# ferrofluide_COUAPEL.net
KiCad netlist of a schematic drawn in EAGLE
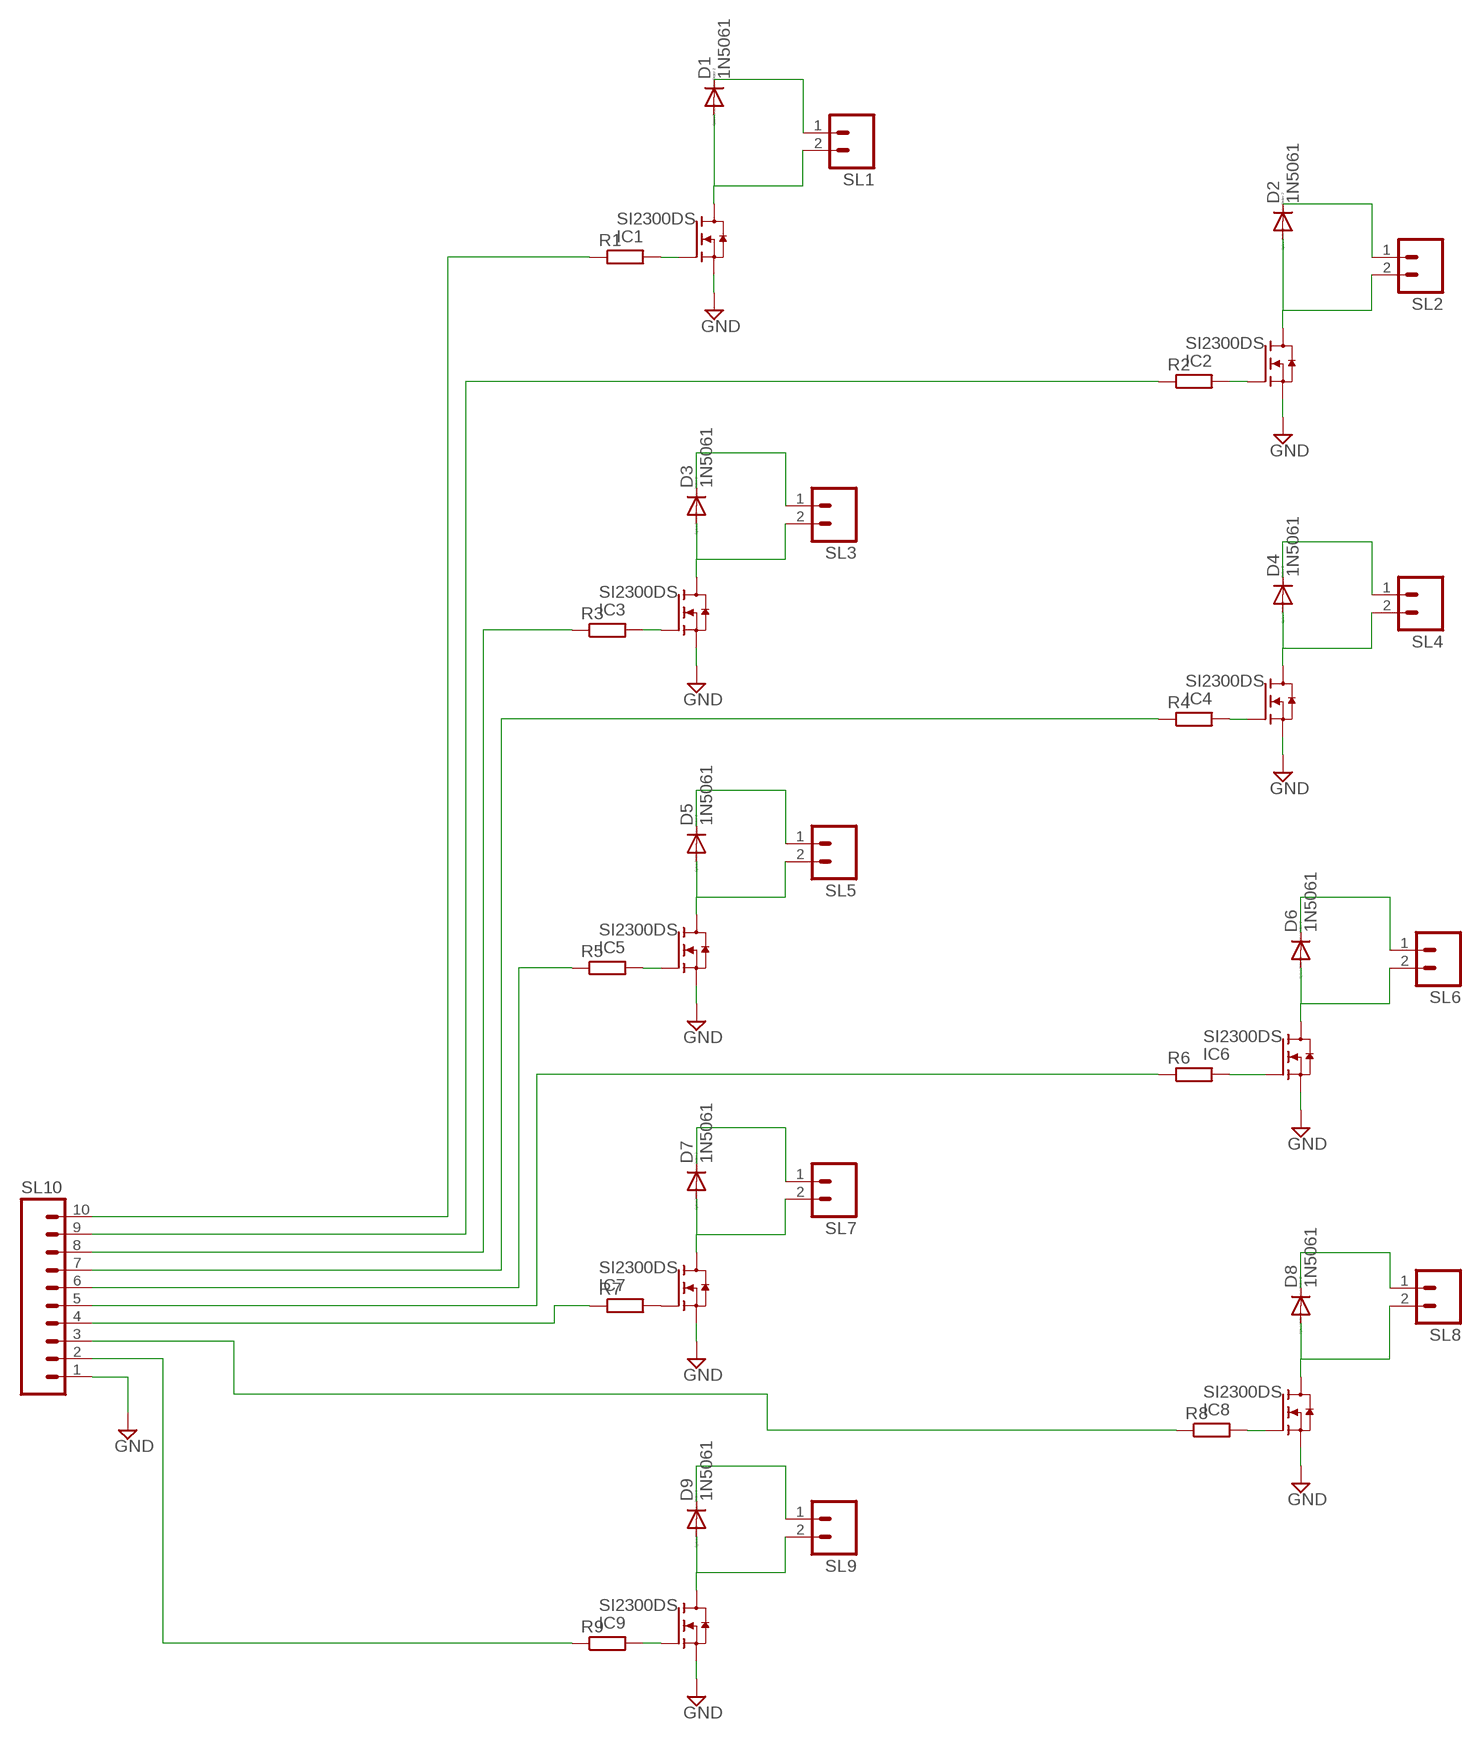
[diagram p0: schematic, sheet 1]

(export (version "E")
  (design (tool "Eeschema 10.0.6"))
  (components
    (comp (ref "D1")
      (value "1N5061")
      (footprint "eagle-import:SOD57-10")
      (libsource (lib "eagle-import") (part "1N5061"))
    )
    (comp (ref "D2")
      (value "1N5061")
      (footprint "eagle-import:SOD57-10")
      (libsource (lib "eagle-import") (part "1N5061"))
    )
    (comp (ref "D3")
      (value "1N5061")
      (footprint "eagle-import:SOD57-10")
      (libsource (lib "eagle-import") (part "1N5061"))
    )
    (comp (ref "D4")
      (value "1N5061")
      (footprint "eagle-import:SOD57-10")
      (libsource (lib "eagle-import") (part "1N5061"))
    )
    (comp (ref "D5")
      (value "1N5061")
      (footprint "eagle-import:SOD57-10")
      (libsource (lib "eagle-import") (part "1N5061"))
    )
    (comp (ref "D6")
      (value "1N5061")
      (footprint "eagle-import:SOD57-10")
      (libsource (lib "eagle-import") (part "1N5061"))
    )
    (comp (ref "D7")
      (value "1N5061")
      (footprint "eagle-import:SOD57-10")
      (libsource (lib "eagle-import") (part "1N5061"))
    )
    (comp (ref "D8")
      (value "1N5061")
      (footprint "eagle-import:SOD57-10")
      (libsource (lib "eagle-import") (part "1N5061"))
    )
    (comp (ref "D9")
      (value "1N5061")
      (footprint "eagle-import:SOD57-10")
      (libsource (lib "eagle-import") (part "1N5061"))
    )
    (comp (ref "IC1")
      (value "SI2300DS")
      (footprint "eagle-import:SOT23")
      (libsource (lib "eagle-import") (part "SI2300DS"))
    )
    (comp (ref "IC2")
      (value "SI2300DS")
      (footprint "eagle-import:SOT23")
      (libsource (lib "eagle-import") (part "SI2300DS"))
    )
    (comp (ref "IC3")
      (value "SI2300DS")
      (footprint "eagle-import:SOT23")
      (libsource (lib "eagle-import") (part "SI2300DS"))
    )
    (comp (ref "IC4")
      (value "SI2300DS")
      (footprint "eagle-import:SOT23")
      (libsource (lib "eagle-import") (part "SI2300DS"))
    )
    (comp (ref "IC5")
      (value "SI2300DS")
      (footprint "eagle-import:SOT23")
      (libsource (lib "eagle-import") (part "SI2300DS"))
    )
    (comp (ref "IC6")
      (value "SI2300DS")
      (footprint "eagle-import:SOT23")
      (libsource (lib "eagle-import") (part "SI2300DS"))
    )
    (comp (ref "IC7")
      (value "SI2300DS")
      (footprint "eagle-import:SOT23")
      (libsource (lib "eagle-import") (part "SI2300DS"))
    )
    (comp (ref "IC8")
      (value "SI2300DS")
      (footprint "eagle-import:SOT23")
      (libsource (lib "eagle-import") (part "SI2300DS"))
    )
    (comp (ref "IC9")
      (value "SI2300DS")
      (footprint "eagle-import:SOT23")
      (libsource (lib "eagle-import") (part "SI2300DS"))
    )
    (comp (ref "R1")
      (value "R-EU_0207/12")
      (footprint "eagle-import:0207_12")
      (libsource (lib "eagle-import") (part "R-EU_0207/12"))
    )
    (comp (ref "R2")
      (value "R-EU_0207/12")
      (footprint "eagle-import:0207_12")
      (libsource (lib "eagle-import") (part "R-EU_0207/12"))
    )
    (comp (ref "R3")
      (value "R-EU_0207/12")
      (footprint "eagle-import:0207_12")
      (libsource (lib "eagle-import") (part "R-EU_0207/12"))
    )
    (comp (ref "R4")
      (value "R-EU_0207/12")
      (footprint "eagle-import:0207_12")
      (libsource (lib "eagle-import") (part "R-EU_0207/12"))
    )
    (comp (ref "R5")
      (value "R-EU_0207/12")
      (footprint "eagle-import:0207_12")
      (libsource (lib "eagle-import") (part "R-EU_0207/12"))
    )
    (comp (ref "R6")
      (value "R-EU_0207/12")
      (footprint "eagle-import:0207_12")
      (libsource (lib "eagle-import") (part "R-EU_0207/12"))
    )
    (comp (ref "R7")
      (value "R-EU_0207/12")
      (footprint "eagle-import:0207_12")
      (libsource (lib "eagle-import") (part "R-EU_0207/12"))
    )
    (comp (ref "R8")
      (value "R-EU_0207/12")
      (footprint "eagle-import:0207_12")
      (libsource (lib "eagle-import") (part "R-EU_0207/12"))
    )
    (comp (ref "R9")
      (value "R-EU_0207/12")
      (footprint "eagle-import:0207_12")
      (libsource (lib "eagle-import") (part "R-EU_0207/12"))
    )
    (comp (ref "SL1")
      (value "M02")
      (footprint "eagle-import:02P")
      (libsource (lib "eagle-import") (part "M02"))
    )
    (comp (ref "SL2")
      (value "M02")
      (footprint "eagle-import:02P")
      (libsource (lib "eagle-import") (part "M02"))
    )
    (comp (ref "SL3")
      (value "M02")
      (footprint "eagle-import:02P")
      (libsource (lib "eagle-import") (part "M02"))
    )
    (comp (ref "SL4")
      (value "M02")
      (footprint "eagle-import:02P")
      (libsource (lib "eagle-import") (part "M02"))
    )
    (comp (ref "SL5")
      (value "M02")
      (footprint "eagle-import:02P")
      (libsource (lib "eagle-import") (part "M02"))
    )
    (comp (ref "SL6")
      (value "M02")
      (footprint "eagle-import:02P")
      (libsource (lib "eagle-import") (part "M02"))
    )
    (comp (ref "SL7")
      (value "M02")
      (footprint "eagle-import:02P")
      (libsource (lib "eagle-import") (part "M02"))
    )
    (comp (ref "SL8")
      (value "M02")
      (footprint "eagle-import:02P")
      (libsource (lib "eagle-import") (part "M02"))
    )
    (comp (ref "SL9")
      (value "M02")
      (footprint "eagle-import:02P")
      (libsource (lib "eagle-import") (part "M02"))
    )
    (comp (ref "SL10")
      (value "M10")
      (footprint "eagle-import:10P")
      (libsource (lib "eagle-import") (part "M10"))
    )
  )
  (nets
    (net (code "1") (name "GND") (class "Default")
      (node (ref "IC1") (pin "2") (pinfunction "S_2") (pintype "passive"))
      (node (ref "IC2") (pin "2") (pinfunction "S_2") (pintype "passive"))
      (node (ref "IC3") (pin "2") (pinfunction "S_2") (pintype "passive"))
      (node (ref "IC4") (pin "2") (pinfunction "S_2") (pintype "passive"))
      (node (ref "IC5") (pin "2") (pinfunction "S_2") (pintype "passive"))
      (node (ref "IC6") (pin "2") (pinfunction "S_2") (pintype "passive"))
      (node (ref "IC7") (pin "2") (pinfunction "S_2") (pintype "passive"))
      (node (ref "IC8") (pin "2") (pinfunction "S_2") (pintype "passive"))
      (node (ref "IC9") (pin "2") (pinfunction "S_2") (pintype "passive"))
      (node (ref "SL10") (pin "1") (pinfunction "1_1") (pintype "passive"))
    )
    (net (code "2") (name "Net-(D1-PadC)") (class "Default")
      (node (ref "D1") (pin "C") (pinfunction "C_C") (pintype "passive"))
      (node (ref "SL1") (pin "1") (pinfunction "1_1") (pintype "passive"))
    )
    (net (code "3") (name "Net-(D2-PadC)") (class "Default")
      (node (ref "D2") (pin "C") (pinfunction "C_C") (pintype "passive"))
      (node (ref "SL2") (pin "1") (pinfunction "1_1") (pintype "passive"))
    )
    (net (code "4") (name "Net-(D3-PadC)") (class "Default")
      (node (ref "D3") (pin "C") (pinfunction "C_C") (pintype "passive"))
      (node (ref "SL3") (pin "1") (pinfunction "1_1") (pintype "passive"))
    )
    (net (code "5") (name "Net-(D4-PadC)") (class "Default")
      (node (ref "D4") (pin "C") (pinfunction "C_C") (pintype "passive"))
      (node (ref "SL4") (pin "1") (pinfunction "1_1") (pintype "passive"))
    )
    (net (code "6") (name "Net-(D5-PadC)") (class "Default")
      (node (ref "D5") (pin "C") (pinfunction "C_C") (pintype "passive"))
      (node (ref "SL5") (pin "1") (pinfunction "1_1") (pintype "passive"))
    )
    (net (code "7") (name "Net-(D6-PadC)") (class "Default")
      (node (ref "D6") (pin "C") (pinfunction "C_C") (pintype "passive"))
      (node (ref "SL6") (pin "1") (pinfunction "1_1") (pintype "passive"))
    )
    (net (code "8") (name "Net-(D7-PadC)") (class "Default")
      (node (ref "D7") (pin "C") (pinfunction "C_C") (pintype "passive"))
      (node (ref "SL7") (pin "1") (pinfunction "1_1") (pintype "passive"))
    )
    (net (code "9") (name "Net-(D8-PadC)") (class "Default")
      (node (ref "D8") (pin "C") (pinfunction "C_C") (pintype "passive"))
      (node (ref "SL8") (pin "1") (pinfunction "1_1") (pintype "passive"))
    )
    (net (code "10") (name "Net-(D9-PadC)") (class "Default")
      (node (ref "D9") (pin "C") (pinfunction "C_C") (pintype "passive"))
      (node (ref "SL9") (pin "1") (pinfunction "1_1") (pintype "passive"))
    )
    (net (code "11") (name "Net-(IC1-D)") (class "Default")
      (node (ref "D1") (pin "A") (pinfunction "A_A") (pintype "passive"))
      (node (ref "IC1") (pin "3") (pinfunction "D_3") (pintype "passive"))
      (node (ref "SL1") (pin "2") (pinfunction "2_2") (pintype "passive"))
    )
    (net (code "12") (name "Net-(IC1-G)") (class "Default")
      (node (ref "IC1") (pin "1") (pinfunction "G_1") (pintype "passive"))
      (node (ref "R1") (pin "2") (pinfunction "2_2") (pintype "passive"))
    )
    (net (code "13") (name "Net-(IC2-D)") (class "Default")
      (node (ref "D2") (pin "A") (pinfunction "A_A") (pintype "passive"))
      (node (ref "IC2") (pin "3") (pinfunction "D_3") (pintype "passive"))
      (node (ref "SL2") (pin "2") (pinfunction "2_2") (pintype "passive"))
    )
    (net (code "14") (name "Net-(IC2-G)") (class "Default")
      (node (ref "IC2") (pin "1") (pinfunction "G_1") (pintype "passive"))
      (node (ref "R2") (pin "2") (pinfunction "2_2") (pintype "passive"))
    )
    (net (code "15") (name "Net-(IC3-D)") (class "Default")
      (node (ref "D3") (pin "A") (pinfunction "A_A") (pintype "passive"))
      (node (ref "IC3") (pin "3") (pinfunction "D_3") (pintype "passive"))
      (node (ref "SL3") (pin "2") (pinfunction "2_2") (pintype "passive"))
    )
    (net (code "16") (name "Net-(IC3-G)") (class "Default")
      (node (ref "IC3") (pin "1") (pinfunction "G_1") (pintype "passive"))
      (node (ref "R3") (pin "2") (pinfunction "2_2") (pintype "passive"))
    )
    (net (code "17") (name "Net-(IC4-D)") (class "Default")
      (node (ref "D4") (pin "A") (pinfunction "A_A") (pintype "passive"))
      (node (ref "IC4") (pin "3") (pinfunction "D_3") (pintype "passive"))
      (node (ref "SL4") (pin "2") (pinfunction "2_2") (pintype "passive"))
    )
    (net (code "18") (name "Net-(IC4-G)") (class "Default")
      (node (ref "IC4") (pin "1") (pinfunction "G_1") (pintype "passive"))
      (node (ref "R4") (pin "2") (pinfunction "2_2") (pintype "passive"))
    )
    (net (code "19") (name "Net-(IC5-D)") (class "Default")
      (node (ref "D5") (pin "A") (pinfunction "A_A") (pintype "passive"))
      (node (ref "IC5") (pin "3") (pinfunction "D_3") (pintype "passive"))
      (node (ref "SL5") (pin "2") (pinfunction "2_2") (pintype "passive"))
    )
    (net (code "20") (name "Net-(IC5-G)") (class "Default")
      (node (ref "IC5") (pin "1") (pinfunction "G_1") (pintype "passive"))
      (node (ref "R5") (pin "2") (pinfunction "2_2") (pintype "passive"))
    )
    (net (code "21") (name "Net-(IC6-D)") (class "Default")
      (node (ref "D6") (pin "A") (pinfunction "A_A") (pintype "passive"))
      (node (ref "IC6") (pin "3") (pinfunction "D_3") (pintype "passive"))
      (node (ref "SL6") (pin "2") (pinfunction "2_2") (pintype "passive"))
    )
    (net (code "22") (name "Net-(IC6-G)") (class "Default")
      (node (ref "IC6") (pin "1") (pinfunction "G_1") (pintype "passive"))
      (node (ref "R6") (pin "2") (pinfunction "2_2") (pintype "passive"))
    )
    (net (code "23") (name "Net-(IC7-D)") (class "Default")
      (node (ref "D7") (pin "A") (pinfunction "A_A") (pintype "passive"))
      (node (ref "IC7") (pin "3") (pinfunction "D_3") (pintype "passive"))
      (node (ref "SL7") (pin "2") (pinfunction "2_2") (pintype "passive"))
    )
    (net (code "24") (name "Net-(IC7-G)") (class "Default")
      (node (ref "IC7") (pin "1") (pinfunction "G_1") (pintype "passive"))
      (node (ref "R7") (pin "2") (pinfunction "2_2") (pintype "passive"))
    )
    (net (code "25") (name "Net-(IC8-D)") (class "Default")
      (node (ref "D8") (pin "A") (pinfunction "A_A") (pintype "passive"))
      (node (ref "IC8") (pin "3") (pinfunction "D_3") (pintype "passive"))
      (node (ref "SL8") (pin "2") (pinfunction "2_2") (pintype "passive"))
    )
    (net (code "26") (name "Net-(IC8-G)") (class "Default")
      (node (ref "IC8") (pin "1") (pinfunction "G_1") (pintype "passive"))
      (node (ref "R8") (pin "2") (pinfunction "2_2") (pintype "passive"))
    )
    (net (code "27") (name "Net-(IC9-D)") (class "Default")
      (node (ref "D9") (pin "A") (pinfunction "A_A") (pintype "passive"))
      (node (ref "IC9") (pin "3") (pinfunction "D_3") (pintype "passive"))
      (node (ref "SL9") (pin "2") (pinfunction "2_2") (pintype "passive"))
    )
    (net (code "28") (name "Net-(IC9-G)") (class "Default")
      (node (ref "IC9") (pin "1") (pinfunction "G_1") (pintype "passive"))
      (node (ref "R9") (pin "2") (pinfunction "2_2") (pintype "passive"))
    )
    (net (code "29") (name "Net-(R1-Pad1)") (class "Default")
      (node (ref "R1") (pin "1") (pinfunction "1_1") (pintype "passive"))
      (node (ref "SL10") (pin "10") (pinfunction "10_10") (pintype "passive"))
    )
    (net (code "30") (name "Net-(R2-Pad1)") (class "Default")
      (node (ref "R2") (pin "1") (pinfunction "1_1") (pintype "passive"))
      (node (ref "SL10") (pin "9") (pinfunction "9_9") (pintype "passive"))
    )
    (net (code "31") (name "Net-(R3-Pad1)") (class "Default")
      (node (ref "R3") (pin "1") (pinfunction "1_1") (pintype "passive"))
      (node (ref "SL10") (pin "8") (pinfunction "8_8") (pintype "passive"))
    )
    (net (code "32") (name "Net-(R4-Pad1)") (class "Default")
      (node (ref "R4") (pin "1") (pinfunction "1_1") (pintype "passive"))
      (node (ref "SL10") (pin "7") (pinfunction "7_7") (pintype "passive"))
    )
    (net (code "33") (name "Net-(R5-Pad1)") (class "Default")
      (node (ref "R5") (pin "1") (pinfunction "1_1") (pintype "passive"))
      (node (ref "SL10") (pin "6") (pinfunction "6_6") (pintype "passive"))
    )
    (net (code "34") (name "Net-(R6-Pad1)") (class "Default")
      (node (ref "R6") (pin "1") (pinfunction "1_1") (pintype "passive"))
      (node (ref "SL10") (pin "5") (pinfunction "5_5") (pintype "passive"))
    )
    (net (code "35") (name "Net-(R7-Pad1)") (class "Default")
      (node (ref "R7") (pin "1") (pinfunction "1_1") (pintype "passive"))
      (node (ref "SL10") (pin "4") (pinfunction "4_4") (pintype "passive"))
    )
    (net (code "36") (name "Net-(R8-Pad1)") (class "Default")
      (node (ref "R8") (pin "1") (pinfunction "1_1") (pintype "passive"))
      (node (ref "SL10") (pin "3") (pinfunction "3_3") (pintype "passive"))
    )
    (net (code "37") (name "Net-(R9-Pad1)") (class "Default")
      (node (ref "R9") (pin "1") (pinfunction "1_1") (pintype "passive"))
      (node (ref "SL10") (pin "2") (pinfunction "2_2") (pintype "passive"))
    )
  )
)
